# PWM_v2_0.net
KiCad netlist of a schematic drawn in EAGLE
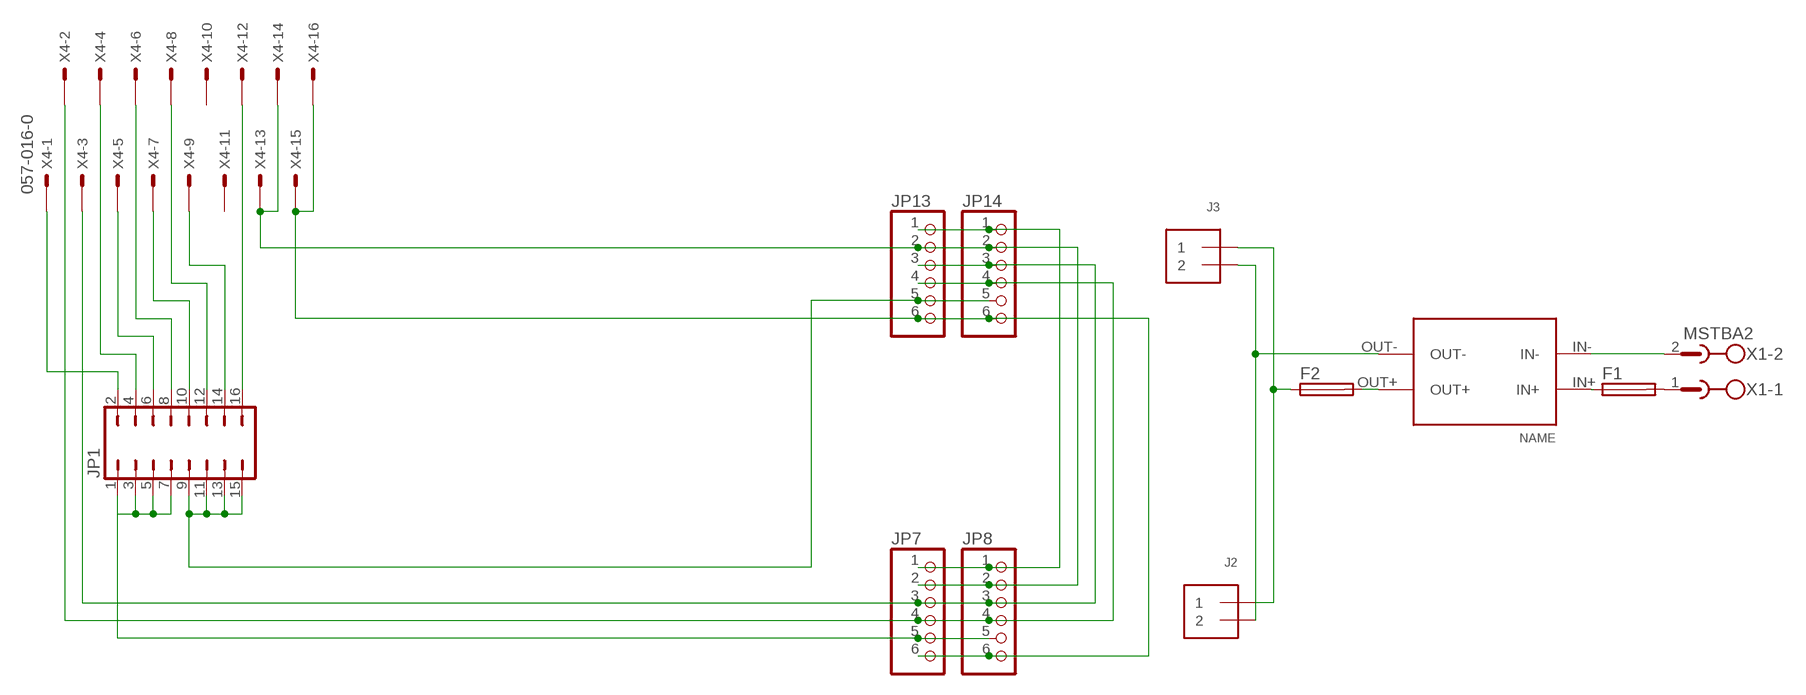
[diagram p0: schematic, sheet 1]

(export (version "E")
  (design (tool "Eeschema 10.0.6"))
  (components
    (comp (ref "F1")
      (value "SH25")
      (footprint "eagle-import:SH25")
      (fields (field (name "MF") "SCHURTER") (field (name "MPN") "0031.8211"))
      (libsource (lib "eagle-import") (part "SH25"))
    )
    (comp (ref "F2")
      (value "SH25")
      (footprint "eagle-import:SH25")
      (fields (field (name "MF") "SCHURTER") (field (name "MPN") "0031.8211"))
      (libsource (lib "eagle-import") (part "SH25"))
    )
    (comp (ref "J2")
      (value "TERMBLOCK_1X2")
      (footprint "eagle-import:TERMBLOCK_1X2-3.5MM")
      (libsource (lib "eagle-import") (part "TERMBLOCK_1X2"))
    )
    (comp (ref "J3")
      (value "TERMBLOCK_1X2")
      (footprint "eagle-import:TERMBLOCK_1X2-3.5MM")
      (libsource (lib "eagle-import") (part "TERMBLOCK_1X2"))
    )
    (comp (ref "JP1")
      (value "JP8Q")
      (footprint "eagle-import:JP8Q")
      (libsource (lib "eagle-import") (part "JP8Q"))
    )
    (comp (ref "JP7")
      (value "PINHD-1X6CB")
      (footprint "eagle-import:1X06-CLEANBIG")
      (libsource (lib "eagle-import") (part "PINHD-1X6CB"))
    )
    (comp (ref "JP8")
      (value "PINHD-1X6CB")
      (footprint "eagle-import:1X06-CLEANBIG")
      (libsource (lib "eagle-import") (part "PINHD-1X6CB"))
    )
    (comp (ref "JP13")
      (value "PINHD-1X6CB")
      (footprint "eagle-import:1X06-CLEANBIG")
      (libsource (lib "eagle-import") (part "PINHD-1X6CB"))
    )
    (comp (ref "JP14")
      (value "PINHD-1X6CB")
      (footprint "eagle-import:1X06-CLEANBIG")
      (libsource (lib "eagle-import") (part "PINHD-1X6CB"))
    )
    (comp (ref "U$2")
      (value "CP8-ADJ")
      (footprint "eagle-import:CP8-ADJ")
      (libsource (lib "eagle-import") (part "CP8-ADJ"))
    )
    (comp (ref "X1")
      (value "MSTBA2")
      (footprint "eagle-import:MSTBA2")
      (fields (field (name "MF") "FARNELL") (field (name "MPN") "1757242"))
      (libsource (lib "eagle-import") (part "MSTBA2"))
    )
    (comp (ref "X4")
      (value "057-016-0")
      (footprint "eagle-import:057-016-0")
      (libsource (lib "eagle-import") (part "057-016-0"))
    )
  )
  (nets
    (net (code "1") (name "Net-(F1-Pad1)") (class "Default")
      (node (ref "F1") (pin "1") (pinfunction "1_1") (pintype "passive"))
      (node (ref "U$2") (pin "IN+") (pinfunction "IN+_IN+") (pintype "passive"))
    )
    (net (code "2") (name "Net-(F1-Pad2)") (class "Default")
      (node (ref "F1") (pin "2") (pinfunction "2_2") (pintype "passive"))
      (node (ref "X1") (pin "1") (pinfunction "1_1") (pintype "passive"))
    )
    (net (code "3") (name "Net-(F2-Pad1)") (class "Default")
      (node (ref "F2") (pin "1") (pinfunction "1_1") (pintype "passive"))
      (node (ref "J2") (pin "1") (pinfunction "1_1") (pintype "passive"))
      (node (ref "J3") (pin "1") (pinfunction "1_1") (pintype "passive"))
    )
    (net (code "4") (name "Net-(F2-Pad2)") (class "Default")
      (node (ref "F2") (pin "2") (pinfunction "2_2") (pintype "passive"))
      (node (ref "U$2") (pin "OUT+") (pinfunction "OUT+_OUT+") (pintype "passive"))
    )
    (net (code "5") (name "Net-(J2-Pad2)") (class "Default")
      (node (ref "J2") (pin "2") (pinfunction "2_2") (pintype "passive"))
      (node (ref "J3") (pin "2") (pinfunction "2_2") (pintype "passive"))
      (node (ref "U$2") (pin "OUT-") (pinfunction "OUT-_OUT-") (pintype "passive"))
    )
    (net (code "6") (name "Net-(JP1-Pad1)") (class "Default")
      (node (ref "JP1") (pin "1") (pinfunction "1_1") (pintype "passive"))
      (node (ref "JP1") (pin "3") (pinfunction "3_3") (pintype "passive"))
      (node (ref "JP1") (pin "5") (pinfunction "5_5") (pintype "passive"))
      (node (ref "JP1") (pin "7") (pinfunction "7_7") (pintype "passive"))
      (node (ref "JP7") (pin "5") (pinfunction "5_5") (pintype "passive"))
      (node (ref "JP8") (pin "5") (pinfunction "5_5") (pintype "passive"))
    )
    (net (code "7") (name "Net-(JP1-Pad11)") (class "Default")
      (node (ref "JP1") (pin "11") (pinfunction "11_11") (pintype "passive"))
      (node (ref "JP1") (pin "13") (pinfunction "13_13") (pintype "passive"))
      (node (ref "JP1") (pin "15") (pinfunction "15_15") (pintype "passive"))
      (node (ref "JP1") (pin "9") (pinfunction "9_9") (pintype "passive"))
      (node (ref "JP13") (pin "5") (pinfunction "5_5") (pintype "passive"))
      (node (ref "JP14") (pin "5") (pinfunction "5_5") (pintype "passive"))
    )
    (net (code "8") (name "Net-(JP13-Pad1)") (class "Default")
      (node (ref "JP13") (pin "1") (pinfunction "1_1") (pintype "passive"))
      (node (ref "JP14") (pin "1") (pinfunction "1_1") (pintype "passive"))
      (node (ref "JP7") (pin "1") (pinfunction "1_1") (pintype "passive"))
      (node (ref "JP8") (pin "1") (pinfunction "1_1") (pintype "passive"))
    )
    (net (code "9") (name "Net-(X1B-1)") (class "Default")
      (node (ref "U$2") (pin "IN-") (pinfunction "IN-_IN-") (pintype "passive"))
      (node (ref "X1") (pin "2") (pinfunction "1_2") (pintype "passive"))
    )
    (net (code "10") (name "Net-(X4A-S)") (class "Default")
      (node (ref "JP1") (pin "2") (pinfunction "2_2") (pintype "passive"))
      (node (ref "X4") (pin "1") (pinfunction "S_1") (pintype "passive"))
    )
    (net (code "11") (name "Net-(X4D-S)") (class "Default")
      (node (ref "JP1") (pin "16") (pinfunction "16_16") (pintype "passive"))
      (node (ref "X4") (pin "12") (pinfunction "S_12") (pintype "passive"))
    )
    (net (code "12") (name "Net-(X4E-S)") (class "Default")
      (node (ref "JP13") (pin "2") (pinfunction "2_2") (pintype "passive"))
      (node (ref "JP14") (pin "2") (pinfunction "2_2") (pintype "passive"))
      (node (ref "JP7") (pin "2") (pinfunction "2_2") (pintype "passive"))
      (node (ref "JP8") (pin "2") (pinfunction "2_2") (pintype "passive"))
      (node (ref "X4") (pin "13") (pinfunction "S_13") (pintype "passive"))
      (node (ref "X4") (pin "14") (pinfunction "S_14") (pintype "passive"))
    )
    (net (code "13") (name "Net-(X4G-S)") (class "Default")
      (node (ref "JP13") (pin "6") (pinfunction "6_6") (pintype "passive"))
      (node (ref "JP14") (pin "6") (pinfunction "6_6") (pintype "passive"))
      (node (ref "JP7") (pin "6") (pinfunction "6_6") (pintype "passive"))
      (node (ref "JP8") (pin "6") (pinfunction "6_6") (pintype "passive"))
      (node (ref "X4") (pin "15") (pinfunction "S_15") (pintype "passive"))
      (node (ref "X4") (pin "16") (pinfunction "S_16") (pintype "passive"))
    )
    (net (code "14") (name "Net-(X4I-S)") (class "Default")
      (node (ref "JP13") (pin "4") (pinfunction "4_4") (pintype "passive"))
      (node (ref "JP14") (pin "4") (pinfunction "4_4") (pintype "passive"))
      (node (ref "JP7") (pin "4") (pinfunction "4_4") (pintype "passive"))
      (node (ref "JP8") (pin "4") (pinfunction "4_4") (pintype "passive"))
      (node (ref "X4") (pin "2") (pinfunction "S_2") (pintype "passive"))
    )
    (net (code "15") (name "Net-(X4J-S)") (class "Default")
      (node (ref "JP13") (pin "3") (pinfunction "3_3") (pintype "passive"))
      (node (ref "JP14") (pin "3") (pinfunction "3_3") (pintype "passive"))
      (node (ref "JP7") (pin "3") (pinfunction "3_3") (pintype "passive"))
      (node (ref "JP8") (pin "3") (pinfunction "3_3") (pintype "passive"))
      (node (ref "X4") (pin "3") (pinfunction "S_3") (pintype "passive"))
    )
    (net (code "16") (name "Net-(X4K-S)") (class "Default")
      (node (ref "JP1") (pin "4") (pinfunction "4_4") (pintype "passive"))
      (node (ref "X4") (pin "4") (pinfunction "S_4") (pintype "passive"))
    )
    (net (code "17") (name "Net-(X4L-S)") (class "Default")
      (node (ref "JP1") (pin "6") (pinfunction "6_6") (pintype "passive"))
      (node (ref "X4") (pin "5") (pinfunction "S_5") (pintype "passive"))
    )
    (net (code "18") (name "Net-(X4M-S)") (class "Default")
      (node (ref "JP1") (pin "8") (pinfunction "8_8") (pintype "passive"))
      (node (ref "X4") (pin "6") (pinfunction "S_6") (pintype "passive"))
    )
    (net (code "19") (name "Net-(X4N-S)") (class "Default")
      (node (ref "JP1") (pin "10") (pinfunction "10_10") (pintype "passive"))
      (node (ref "X4") (pin "7") (pinfunction "S_7") (pintype "passive"))
    )
    (net (code "20") (name "Net-(X4O-S)") (class "Default")
      (node (ref "JP1") (pin "12") (pinfunction "12_12") (pintype "passive"))
      (node (ref "X4") (pin "8") (pinfunction "S_8") (pintype "passive"))
    )
    (net (code "21") (name "Net-(X4P-S)") (class "Default")
      (node (ref "JP1") (pin "14") (pinfunction "14_14") (pintype "passive"))
      (node (ref "X4") (pin "9") (pinfunction "S_9") (pintype "passive"))
    )
    (net (code "22") (name "unconnected-(X4B-S-Pad10)") (class "Default")
      (node (ref "X4") (pin "10") (pinfunction "S_10") (pintype "passive"))
    )
    (net (code "23") (name "unconnected-(X4C-S-Pad11)") (class "Default")
      (node (ref "X4") (pin "11") (pinfunction "S_11") (pintype "passive"))
    )
  )
)
